# Sheet4_CAN_Interface.net
KiCad netlist of a schematic drawn in Altium Designer
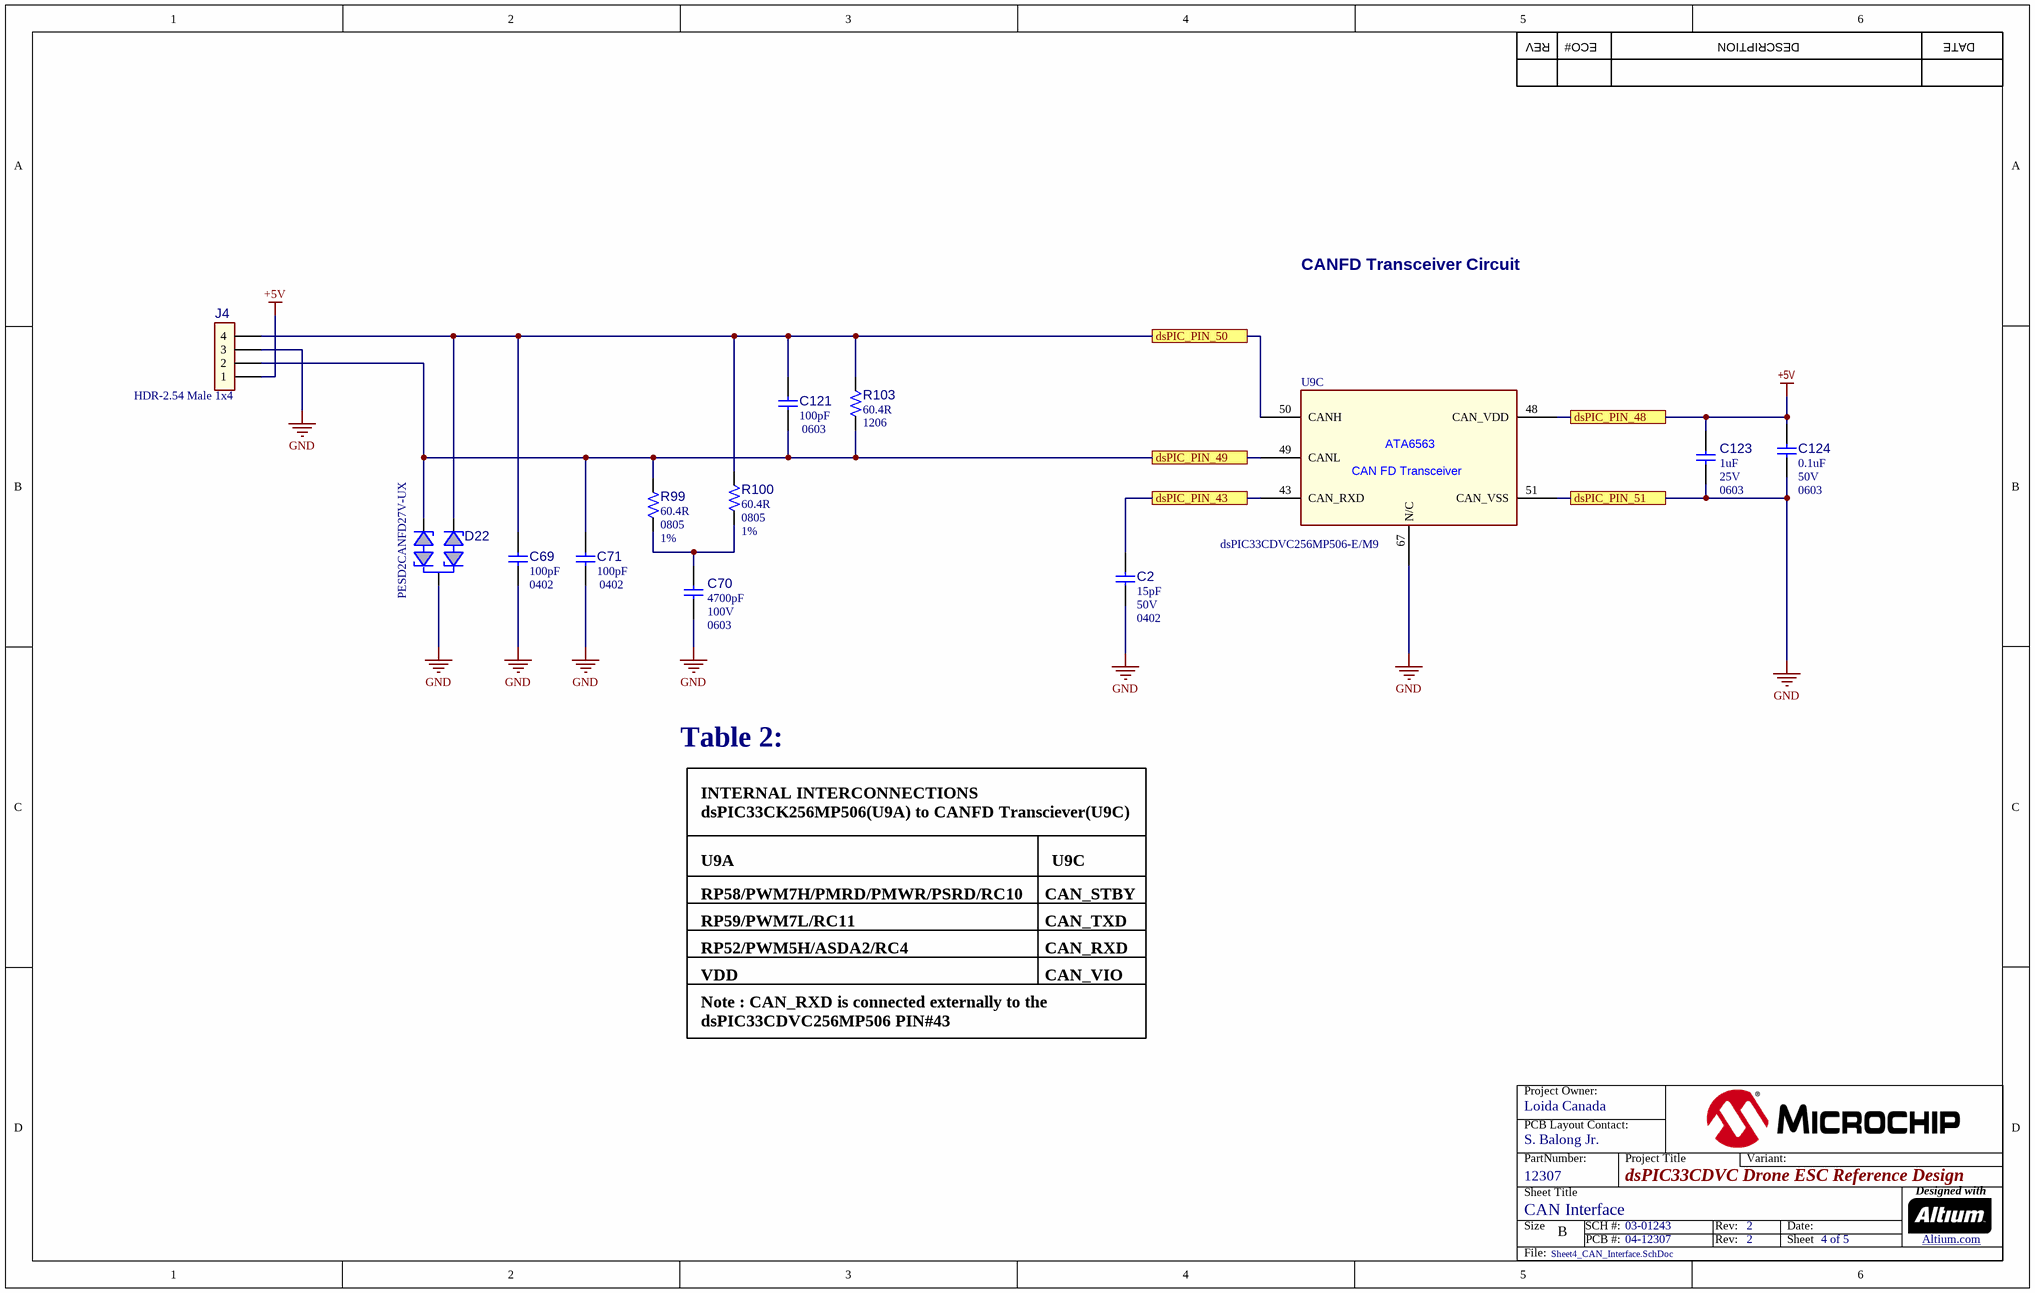
[diagram p0: Sheet4_CAN_Interface.SchDoc]

(export (version "E")
  (design (tool "Eeschema 10.0.6"))
  (components
    (comp (ref "C2")
      (value "15pF")
      (footprint "CAP_C_0402")
      (fields
        (field (name "VOLTAGE") "50V")
        (field (name "PACKAGE") "0402")
        (field (name "TOLERANCE") "5%")
        (field (name "Comment") "Capacitor NP")
      )
      (libsource (lib "MCHP-CDB") (part "Capacitor NP"))
    )
    (comp (ref "C69")
      (value "100pF")
      (footprint "CAP_C_0402")
      (fields
        (field (name "VOLTAGE") "50V")
        (field (name "PACKAGE") "0402")
        (field (name "TOLERANCE") "5%")
        (field (name "Comment") "Capacitor NP")
        (field (name "OWNER") "Sompoch Loboonlert")
      )
      (libsource (lib "MCHP-CDB") (part "Capacitor NP"))
    )
    (comp (ref "C70")
      (value "4700pF")
      (footprint "CAP_C_0603")
      (fields
        (field (name "VOLTAGE") "100V")
        (field (name "PACKAGE") "0603")
        (field (name "TOLERANCE") "10%")
        (field (name "Comment") "Capacitor NP")
        (field (name "OWNER") "Narasimha Murthy")
      )
      (libsource (lib "MCHP-CDB") (part "Capacitor NP"))
    )
    (comp (ref "C71")
      (value "100pF")
      (footprint "CAP_C_0402")
      (fields
        (field (name "VOLTAGE") "50V")
        (field (name "PACKAGE") "0402")
        (field (name "TOLERANCE") "5%")
        (field (name "Comment") "Capacitor NP")
        (field (name "OWNER") "Sompoch Loboonlert")
      )
      (libsource (lib "MCHP-CDB") (part "Capacitor NP"))
    )
    (comp (ref "C121")
      (value "100pF")
      (footprint "CAP_C_0603")
      (fields
        (field (name "VOLTAGE") "100V")
        (field (name "PACKAGE") "0603")
        (field (name "TOLERANCE") "5%")
        (field (name "Comment") "Capacitor NP")
        (field (name "OWNER") "Mihai T(M91442)")
      )
      (libsource (lib "MCHP-CDB") (part "Capacitor NP"))
    )
    (comp (ref "C123")
      (value "1uF")
      (footprint "CAP_C_0603")
      (fields
        (field (name "VOLTAGE") "25V")
        (field (name "PACKAGE") "0603")
        (field (name "TOLERANCE") "10%")
        (field (name "Comment") "Capacitor NP")
        (field (name "OWNER") "Sompoch Loboonlert")
      )
      (libsource (lib "MCHP-CDB") (part "Capacitor NP"))
    )
    (comp (ref "C124")
      (value "0.1uF")
      (footprint "CAP_C_0603")
      (fields
        (field (name "VOLTAGE") "50V")
        (field (name "PACKAGE") "0603")
        (field (name "TOLERANCE") "±10%")
        (field (name "Comment") "Capacitor NP")
        (field (name "OWNER") "Jose Garcia")
      )
      (libsource (lib "MCHP-CDB") (part "Capacitor NP"))
    )
    (comp (ref "D22")
      (value "Diode K1K2CC ESD Bidirectional")
      (footprint "SOT-323-3")
      (fields
        (field (name "MANUFACTURER PART NUMBER 1") "PESD2CANFD27V-UX")
        (field (name "OWNER") "Narasimha Murthy")
      )
      (libsource (lib "MCHP-CDB") (part "Diode K1K2CC ESD Bidirectional"))
    )
    (comp (ref "J4")
      (value "HDR-2.54 Male 1x4")
      (footprint "HDR_M_2.54_1x4")
      (fields (field (name "Comment") "Header 1x4"))
      (libsource (lib "MCHP-CDB") (part "Header 1x4"))
    )
    (comp (ref "R99")
      (value "60.4R")
      (footprint "RES_C_0805")
      (description "Resistor")
      (fields
        (field (name "PACKAGE") "0805")
        (field (name "TOLERANCE") "1%")
        (field (name "POWER") "1/2W")
        (field (name "OWNER") "Severino Balong Jr.")
      )
      (libsource (lib "") (part "Resistor_1"))
    )
    (comp (ref "R100")
      (value "60.4R")
      (footprint "RES_C_0805")
      (description "Resistor")
      (fields
        (field (name "PACKAGE") "0805")
        (field (name "TOLERANCE") "1%")
        (field (name "POWER") "1/2W")
        (field (name "OWNER") "Severino Balong Jr.")
      )
      (libsource (lib "") (part "Resistor_1"))
    )
    (comp (ref "R103")
      (value "60.4R")
      (footprint "RES_C_1206")
      (description "Resistor")
      (fields
        (field (name "PACKAGE") "1206")
        (field (name "TOLERANCE") "0.1%")
        (field (name "VOLTAGE") "200V")
        (field (name "OWNER") "Narasimha Murthy")
      )
      (libsource (lib "MCHP-CDB") (part "Resistor"))
    )
    (comp (ref "U9")
      (value "dsPIC33CDVC256MP506-E/M9")
      (footprint "QFN-64_9X9_3EP_M9")
      (fields
        (field (name "Comment") "dsPIC33CDVC256MP506_VGQFN-64")
        (field (name "OWNER") "Narasimha Murthy")
      )
      (libsource (lib "MCHP-CDB") (part "dsPIC33CDVC256MP506_VGQFN-64"))
    )
  )
  (nets
    (net (code "1") (name "+5V") (class "Default")
      (node (ref "C123") (pin "1") (pinfunction "1_1") (pintype "passive"))
      (node (ref "C124") (pin "2") (pinfunction "2_2") (pintype "passive"))
      (node (ref "J4") (pin "1") (pinfunction "1_1") (pintype "passive"))
      (node (ref "U9") (pin "48") (pinfunction "CAN_VDD_48") (pintype "passive"))
    )
    (net (code "2") (name "/dsPIC_PIN_43") (class "Default")
      (node (ref "C2") (pin "2") (pinfunction "2_2") (pintype "passive"))
      (node (ref "U9") (pin "43") (pinfunction "CAN_RXD_43") (pintype "passive"))
    )
    (net (code "3") (name "/dsPIC_PIN_49") (class "Default")
      (node (ref "C121") (pin "1") (pinfunction "1_1") (pintype "passive"))
      (node (ref "C71") (pin "1") (pinfunction "1_1") (pintype "passive"))
      (node (ref "D22") (pin "1") (pinfunction "K1_1") (pintype "passive"))
      (node (ref "J4") (pin "2") (pinfunction "2_2") (pintype "passive"))
      (node (ref "R103") (pin "1") (pinfunction "1_1") (pintype "passive"))
      (node (ref "R99") (pin "2") (pinfunction "2_2") (pintype "passive"))
      (node (ref "U9") (pin "49") (pinfunction "CANL_49") (pintype "passive"))
    )
    (net (code "4") (name "/dsPIC_PIN_50") (class "Default")
      (node (ref "C121") (pin "2") (pinfunction "2_2") (pintype "passive"))
      (node (ref "C69") (pin "1") (pinfunction "1_1") (pintype "passive"))
      (node (ref "D22") (pin "2") (pinfunction "K2_2") (pintype "passive"))
      (node (ref "J4") (pin "4") (pinfunction "4_4") (pintype "passive"))
      (node (ref "R100") (pin "2") (pinfunction "2_2") (pintype "passive"))
      (node (ref "R103") (pin "2") (pinfunction "2_2") (pintype "passive"))
      (node (ref "U9") (pin "50") (pinfunction "CANH_50") (pintype "passive"))
    )
    (net (code "5") (name "GND") (class "Default")
      (node (ref "C123") (pin "2") (pinfunction "2_2") (pintype "passive"))
      (node (ref "C124") (pin "1") (pinfunction "1_1") (pintype "passive"))
      (node (ref "C2") (pin "1") (pinfunction "1_1") (pintype "passive"))
      (node (ref "C69") (pin "2") (pinfunction "2_2") (pintype "passive"))
      (node (ref "C70") (pin "1") (pinfunction "1_1") (pintype "passive"))
      (node (ref "C71") (pin "2") (pinfunction "2_2") (pintype "passive"))
      (node (ref "D22") (pin "3") (pinfunction "CC_3") (pintype "passive"))
      (node (ref "J4") (pin "3") (pinfunction "3_3") (pintype "passive"))
      (node (ref "U9") (pin "51") (pinfunction "CAN_VSS_51") (pintype "passive"))
      (node (ref "U9") (pin "67") (pinfunction "N/C_67") (pintype "passive"))
    )
    (net (code "6") (name "Net-(C70-Pad2)") (class "Default")
      (node (ref "C70") (pin "2") (pinfunction "2_2") (pintype "passive"))
      (node (ref "R100") (pin "1") (pinfunction "1_1") (pintype "passive"))
      (node (ref "R99") (pin "1") (pinfunction "1_1") (pintype "passive"))
    )
  )
)
